# POEInjectorTop.net
KiCad netlist of a schematic drawn in Altium Designer
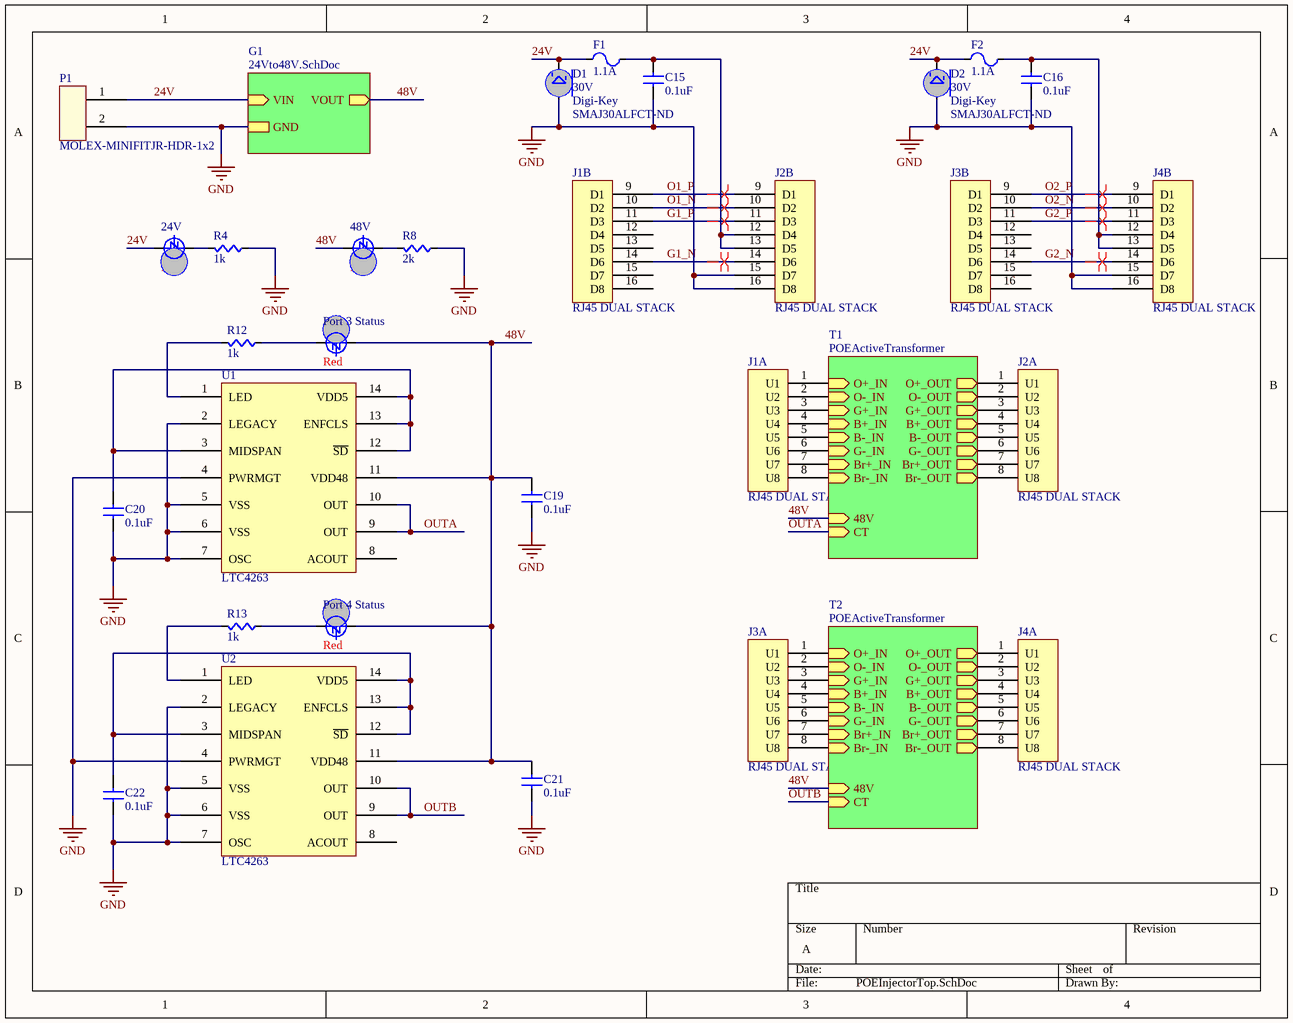
[diagram p0: POEInjectorTop.SchDoc]

(export (version "E")
  (design (tool "Eeschema 10.0.6"))
  (components
    (comp (ref "24V")
      (value "LED")
      (footprint "LED0603")
      (fields (field (name "COLOR") "Red"))
      (libsource (lib "") (part "LED_1"))
    )
    (comp (ref "48V")
      (value "LED")
      (footprint "LED0603")
      (fields (field (name "COLOR") "Red"))
      (libsource (lib "") (part "LED_1"))
    )
    (comp (ref "C15")
      (value "0.1uF")
      (footprint "CAPC0603")
      (fields (field (name "Comment") "Cap"))
      (libsource (lib "Passives") (part "Cap"))
    )
    (comp (ref "C16")
      (value "0.1uF")
      (footprint "CAPC0603")
      (fields (field (name "Comment") "Cap"))
      (libsource (lib "Passives") (part "Cap"))
    )
    (comp (ref "C19")
      (value "0.1uF")
      (footprint "CAPC0603")
      (fields (field (name "Comment") "Cap"))
      (libsource (lib "Passives") (part "Cap"))
    )
    (comp (ref "C20")
      (value "0.1uF")
      (footprint "CAPC0603")
      (fields (field (name "Comment") "Cap"))
      (libsource (lib "Passives") (part "Cap"))
    )
    (comp (ref "C21")
      (value "0.1uF")
      (footprint "CAPC0603")
      (fields (field (name "Comment") "Cap"))
      (libsource (lib "Passives") (part "Cap"))
    )
    (comp (ref "C22")
      (value "0.1uF")
      (footprint "CAPC0603")
      (fields (field (name "Comment") "Cap"))
      (libsource (lib "Passives") (part "Cap"))
    )
    (comp (ref "D1")
      (value "30V")
      (footprint "SMASeries")
      (description "Zener Diode")
      (fields
        (field (name "SUPPLIER 1") "Digi-Key")
        (field (name "SUPPLIER PART NUMBER 1") "SMAJ30ALFCT-ND")
        (field (name "Comment") "Zener")
      )
      (libsource (lib "Semiconductors") (part "Zener"))
    )
    (comp (ref "D2")
      (value "30V")
      (footprint "SMASeries")
      (description "Zener Diode")
      (fields
        (field (name "SUPPLIER 1") "Digi-Key")
        (field (name "SUPPLIER PART NUMBER 1") "SMAJ30ALFCT-ND")
        (field (name "Comment") "Zener")
      )
      (libsource (lib "Semiconductors") (part "Zener"))
    )
    (comp (ref "F1")
      (value "1.1A")
      (footprint "PTC7451X11N")
      (fields (field (name "Comment") "PTC Fuse"))
      (libsource (lib "Passives") (part "PTC_Fuse"))
    )
    (comp (ref "F2")
      (value "1.1A")
      (footprint "PTC7451X11N")
      (fields (field (name "Comment") "PTC Fuse"))
      (libsource (lib "Passives") (part "PTC_Fuse"))
    )
    (comp (ref "J1")
      (value "RJ45 DUAL STACK")
      (footprint "RJ45 DUAL STACK")
      (description "CONN MOD JACK 8P8C R/A SHIELDED")
      (libsource (lib "") (part "RJ45 DUAL STACK_1"))
    )
    (comp (ref "J2")
      (value "RJ45 DUAL STACK")
      (footprint "RJ45 DUAL STACK")
      (description "CONN MOD JACK 8P8C R/A SHIELDED")
      (libsource (lib "Connectors") (part "RJ45 DUAL STACK"))
    )
    (comp (ref "J3")
      (value "RJ45 DUAL STACK")
      (footprint "RJ45 DUAL STACK")
      (description "CONN MOD JACK 8P8C R/A SHIELDED")
      (libsource (lib "") (part "RJ45 DUAL STACK_1"))
    )
    (comp (ref "J4")
      (value "RJ45 DUAL STACK")
      (footprint "RJ45 DUAL STACK")
      (description "CONN MOD JACK 8P8C R/A SHIELDED")
      (libsource (lib "Connectors") (part "RJ45 DUAL STACK"))
    )
    (comp (ref "P1")
      (value "MOLEX-MINIFITJR-HDR-1x2")
      (footprint "MOLEX-MINIFITJR-HDR-1x2")
      (description "MINIFITJRHDR VT DR O/PGS 2POS")
      (libsource (lib "Connectors") (part "MOLEX-MINIFITJR-HDR-1x2"))
    )
    (comp (ref "Port 3 Status")
      (value "LED")
      (footprint "LED0603")
      (fields (field (name "COLOR") "Red"))
      (libsource (lib "Semiconductors") (part "LED"))
    )
    (comp (ref "Port 4 Status")
      (value "LED")
      (footprint "LED0603")
      (fields (field (name "COLOR") "Red"))
      (libsource (lib "Semiconductors") (part "LED"))
    )
    (comp (ref "R4")
      (value "1k")
      (footprint "RES0603")
      (fields (field (name "Comment") "Res"))
      (libsource (lib "Passives") (part "Res"))
    )
    (comp (ref "R8")
      (value "2k")
      (footprint "RES0603")
      (fields (field (name "Comment") "Res"))
      (libsource (lib "Passives") (part "Res"))
    )
    (comp (ref "R12")
      (value "1k")
      (footprint "RES0603")
      (fields (field (name "Comment") "Res"))
      (libsource (lib "Passives") (part "Res"))
    )
    (comp (ref "R13")
      (value "1k")
      (footprint "RES0603")
      (fields (field (name "Comment") "Res"))
      (libsource (lib "Passives") (part "Res"))
    )
    (comp (ref "U1")
      (value "LTC4263")
      (footprint "LTC4263")
      (description "IC POE 803.2AF SINGL PSE 14-SOIC")
      (libsource (lib "ICs") (part "LTC4263"))
    )
    (comp (ref "U2")
      (value "LTC4263")
      (footprint "LTC4263")
      (description "IC POE 803.2AF SINGL PSE 14-SOIC")
      (libsource (lib "ICs") (part "LTC4263"))
    )
  )
  (nets
    (net (code "1") (name "/24V") (class "Default")
      (node (ref "24V") (pin "A") (pinfunction "A_A") (pintype "passive"))
      (node (ref "D1") (pin "C") (pinfunction "C_C") (pintype "passive"))
      (node (ref "D2") (pin "C") (pinfunction "C_C") (pintype "passive"))
      (node (ref "F1") (pin "1") (pinfunction "A_1") (pintype "passive"))
      (node (ref "F2") (pin "1") (pinfunction "A_1") (pintype "passive"))
      (node (ref "P1") (pin "1") (pinfunction "1_1") (pintype "passive"))
    )
    (net (code "2") (name "/48V") (class "Default")
      (node (ref "48V") (pin "A") (pinfunction "A_A") (pintype "passive"))
      (node (ref "C19") (pin "1") (pinfunction "A_1") (pintype "passive"))
      (node (ref "C21") (pin "1") (pinfunction "A_1") (pintype "passive"))
      (node (ref "Port 3 Status") (pin "A") (pinfunction "A_A") (pintype "passive"))
      (node (ref "Port 4 Status") (pin "A") (pinfunction "A_A") (pintype "passive"))
      (node (ref "U1") (pin "11") (pinfunction "VDD48_11") (pintype "passive"))
      (node (ref "U2") (pin "11") (pinfunction "VDD48_11") (pintype "passive"))
    )
    (net (code "3") (name "/B+_IN") (class "Default")
      (node (ref "J3") (pin "4") (pinfunction "U4_4") (pintype "passive"))
    )
    (net (code "4") (name "/B+_IN_1") (class "Default")
      (node (ref "J1") (pin "4") (pinfunction "U4_4") (pintype "passive"))
    )
    (net (code "5") (name "/B+_OUT") (class "Default")
      (node (ref "J4") (pin "4") (pinfunction "U4_4") (pintype "passive"))
    )
    (net (code "6") (name "/B+_OUT_1") (class "Default")
      (node (ref "J2") (pin "4") (pinfunction "U4_4") (pintype "passive"))
    )
    (net (code "7") (name "/B-_IN") (class "Default")
      (node (ref "J3") (pin "5") (pinfunction "U5_5") (pintype "passive"))
    )
    (net (code "8") (name "/B-_IN_1") (class "Default")
      (node (ref "J1") (pin "5") (pinfunction "U5_5") (pintype "passive"))
    )
    (net (code "9") (name "/B-_OUT") (class "Default")
      (node (ref "J4") (pin "5") (pinfunction "U5_5") (pintype "passive"))
    )
    (net (code "10") (name "/B-_OUT_1") (class "Default")
      (node (ref "J2") (pin "5") (pinfunction "U5_5") (pintype "passive"))
    )
    (net (code "11") (name "/Br+_IN") (class "Default")
      (node (ref "J3") (pin "7") (pinfunction "U7_7") (pintype "passive"))
    )
    (net (code "12") (name "/Br+_IN_1") (class "Default")
      (node (ref "J1") (pin "7") (pinfunction "U7_7") (pintype "passive"))
    )
    (net (code "13") (name "/Br+_OUT") (class "Default")
      (node (ref "J4") (pin "7") (pinfunction "U7_7") (pintype "passive"))
    )
    (net (code "14") (name "/Br+_OUT_1") (class "Default")
      (node (ref "J2") (pin "7") (pinfunction "U7_7") (pintype "passive"))
    )
    (net (code "15") (name "/Br-_IN") (class "Default")
      (node (ref "J3") (pin "8") (pinfunction "U8_8") (pintype "passive"))
    )
    (net (code "16") (name "/Br-_IN_1") (class "Default")
      (node (ref "J1") (pin "8") (pinfunction "U8_8") (pintype "passive"))
    )
    (net (code "17") (name "/Br-_OUT") (class "Default")
      (node (ref "J4") (pin "8") (pinfunction "U8_8") (pintype "passive"))
    )
    (net (code "18") (name "/Br-_OUT_1") (class "Default")
      (node (ref "J2") (pin "8") (pinfunction "U8_8") (pintype "passive"))
    )
    (net (code "19") (name "/G+_IN") (class "Default")
      (node (ref "J3") (pin "3") (pinfunction "U3_3") (pintype "passive"))
    )
    (net (code "20") (name "/G+_IN_1") (class "Default")
      (node (ref "J1") (pin "3") (pinfunction "U3_3") (pintype "passive"))
    )
    (net (code "21") (name "/G+_OUT") (class "Default")
      (node (ref "J4") (pin "3") (pinfunction "U3_3") (pintype "passive"))
    )
    (net (code "22") (name "/G+_OUT_1") (class "Default")
      (node (ref "J2") (pin "3") (pinfunction "U3_3") (pintype "passive"))
    )
    (net (code "23") (name "/G-_IN") (class "Default")
      (node (ref "J3") (pin "6") (pinfunction "U6_6") (pintype "passive"))
    )
    (net (code "24") (name "/G-_IN_1") (class "Default")
      (node (ref "J1") (pin "6") (pinfunction "U6_6") (pintype "passive"))
    )
    (net (code "25") (name "/G-_OUT") (class "Default")
      (node (ref "J4") (pin "6") (pinfunction "U6_6") (pintype "passive"))
    )
    (net (code "26") (name "/G-_OUT_1") (class "Default")
      (node (ref "J2") (pin "6") (pinfunction "U6_6") (pintype "passive"))
    )
    (net (code "27") (name "/G1_N") (class "Default")
      (node (ref "J1") (pin "14") (pinfunction "D6_14") (pintype "passive"))
      (node (ref "J2") (pin "14") (pinfunction "D6_14") (pintype "passive"))
    )
    (net (code "28") (name "/G1_P") (class "Default")
      (node (ref "J1") (pin "11") (pinfunction "D3_11") (pintype "passive"))
      (node (ref "J2") (pin "11") (pinfunction "D3_11") (pintype "passive"))
    )
    (net (code "29") (name "/G2_N") (class "Default")
      (node (ref "J3") (pin "14") (pinfunction "D6_14") (pintype "passive"))
      (node (ref "J4") (pin "14") (pinfunction "D6_14") (pintype "passive"))
    )
    (net (code "30") (name "/G2_P") (class "Default")
      (node (ref "J3") (pin "11") (pinfunction "D3_11") (pintype "passive"))
      (node (ref "J4") (pin "11") (pinfunction "D3_11") (pintype "passive"))
    )
    (net (code "31") (name "/O+_IN") (class "Default")
      (node (ref "J3") (pin "1") (pinfunction "U1_1") (pintype "passive"))
    )
    (net (code "32") (name "/O+_IN_1") (class "Default")
      (node (ref "J1") (pin "1") (pinfunction "U1_1") (pintype "passive"))
    )
    (net (code "33") (name "/O+_OUT") (class "Default")
      (node (ref "J4") (pin "1") (pinfunction "U1_1") (pintype "passive"))
    )
    (net (code "34") (name "/O+_OUT_1") (class "Default")
      (node (ref "J2") (pin "1") (pinfunction "U1_1") (pintype "passive"))
    )
    (net (code "35") (name "/O-_IN") (class "Default")
      (node (ref "J3") (pin "2") (pinfunction "U2_2") (pintype "passive"))
    )
    (net (code "36") (name "/O-_IN_1") (class "Default")
      (node (ref "J1") (pin "2") (pinfunction "U2_2") (pintype "passive"))
    )
    (net (code "37") (name "/O-_OUT") (class "Default")
      (node (ref "J4") (pin "2") (pinfunction "U2_2") (pintype "passive"))
    )
    (net (code "38") (name "/O-_OUT_1") (class "Default")
      (node (ref "J2") (pin "2") (pinfunction "U2_2") (pintype "passive"))
    )
    (net (code "39") (name "/O1_N") (class "Default")
      (node (ref "J1") (pin "10") (pinfunction "D2_10") (pintype "passive"))
      (node (ref "J2") (pin "10") (pinfunction "D2_10") (pintype "passive"))
    )
    (net (code "40") (name "/O1_P") (class "Default")
      (node (ref "J1") (pin "9") (pinfunction "D1_9") (pintype "passive"))
      (node (ref "J2") (pin "9") (pinfunction "D1_9") (pintype "passive"))
    )
    (net (code "41") (name "/O2_N") (class "Default")
      (node (ref "J3") (pin "10") (pinfunction "D2_10") (pintype "passive"))
      (node (ref "J4") (pin "10") (pinfunction "D2_10") (pintype "passive"))
    )
    (net (code "42") (name "/O2_P") (class "Default")
      (node (ref "J3") (pin "9") (pinfunction "D1_9") (pintype "passive"))
      (node (ref "J4") (pin "9") (pinfunction "D1_9") (pintype "passive"))
    )
    (net (code "43") (name "/OUTA") (class "Default")
      (node (ref "U1") (pin "10") (pinfunction "OUT_10") (pintype "passive"))
      (node (ref "U1") (pin "9") (pinfunction "OUT_9") (pintype "passive"))
    )
    (net (code "44") (name "/OUTB") (class "Default")
      (node (ref "U2") (pin "10") (pinfunction "OUT_10") (pintype "passive"))
      (node (ref "U2") (pin "9") (pinfunction "OUT_9") (pintype "passive"))
    )
    (net (code "45") (name "GND") (class "Default")
      (node (ref "C15") (pin "2") (pinfunction "B_2") (pintype "passive"))
      (node (ref "C16") (pin "2") (pinfunction "B_2") (pintype "passive"))
      (node (ref "C19") (pin "2") (pinfunction "B_2") (pintype "passive"))
      (node (ref "C20") (pin "2") (pinfunction "B_2") (pintype "passive"))
      (node (ref "C21") (pin "2") (pinfunction "B_2") (pintype "passive"))
      (node (ref "C22") (pin "2") (pinfunction "B_2") (pintype "passive"))
      (node (ref "D1") (pin "A") (pinfunction "A_A") (pintype "passive"))
      (node (ref "D2") (pin "A") (pinfunction "A_A") (pintype "passive"))
      (node (ref "J2") (pin "15") (pinfunction "D7_15") (pintype "passive"))
      (node (ref "J2") (pin "16") (pinfunction "D8_16") (pintype "passive"))
      (node (ref "J4") (pin "15") (pinfunction "D7_15") (pintype "passive"))
      (node (ref "J4") (pin "16") (pinfunction "D8_16") (pintype "passive"))
      (node (ref "P1") (pin "2") (pinfunction "2_2") (pintype "passive"))
      (node (ref "R4") (pin "2") (pinfunction "B_2") (pintype "passive"))
      (node (ref "R8") (pin "2") (pinfunction "B_2") (pintype "passive"))
      (node (ref "U1") (pin "2") (pinfunction "LEGACY_2") (pintype "passive"))
      (node (ref "U1") (pin "4") (pinfunction "PWRMGT_4") (pintype "passive"))
      (node (ref "U1") (pin "5") (pinfunction "VSS_5") (pintype "passive"))
      (node (ref "U1") (pin "6") (pinfunction "VSS_6") (pintype "passive"))
      (node (ref "U1") (pin "7") (pinfunction "OSC_7") (pintype "passive"))
      (node (ref "U2") (pin "2") (pinfunction "LEGACY_2") (pintype "passive"))
      (node (ref "U2") (pin "4") (pinfunction "PWRMGT_4") (pintype "passive"))
      (node (ref "U2") (pin "5") (pinfunction "VSS_5") (pintype "passive"))
      (node (ref "U2") (pin "6") (pinfunction "VSS_6") (pintype "passive"))
      (node (ref "U2") (pin "7") (pinfunction "OSC_7") (pintype "passive"))
    )
    (net (code "46") (name "Net-(C15-A)") (class "Default")
      (node (ref "C15") (pin "1") (pinfunction "A_1") (pintype "passive"))
      (node (ref "F1") (pin "2") (pinfunction "B_2") (pintype "passive"))
      (node (ref "J2") (pin "12") (pinfunction "D4_12") (pintype "passive"))
      (node (ref "J2") (pin "13") (pinfunction "D5_13") (pintype "passive"))
    )
    (net (code "47") (name "Net-(C16-A)") (class "Default")
      (node (ref "C16") (pin "1") (pinfunction "A_1") (pintype "passive"))
      (node (ref "F2") (pin "2") (pinfunction "B_2") (pintype "passive"))
      (node (ref "J4") (pin "12") (pinfunction "D4_12") (pintype "passive"))
      (node (ref "J4") (pin "13") (pinfunction "D5_13") (pintype "passive"))
    )
    (net (code "48") (name "Net-(C20-A)") (class "Default")
      (node (ref "C20") (pin "1") (pinfunction "A_1") (pintype "passive"))
      (node (ref "U1") (pin "12") (pinfunction "~{SD}_12") (pintype "passive"))
      (node (ref "U1") (pin "13") (pinfunction "ENFCLS_13") (pintype "passive"))
      (node (ref "U1") (pin "14") (pinfunction "VDD5_14") (pintype "passive"))
      (node (ref "U1") (pin "3") (pinfunction "MIDSPAN_3") (pintype "passive"))
    )
    (net (code "49") (name "Net-(C22-A)") (class "Default")
      (node (ref "C22") (pin "1") (pinfunction "A_1") (pintype "passive"))
      (node (ref "U2") (pin "12") (pinfunction "~{SD}_12") (pintype "passive"))
      (node (ref "U2") (pin "13") (pinfunction "ENFCLS_13") (pintype "passive"))
      (node (ref "U2") (pin "14") (pinfunction "VDD5_14") (pintype "passive"))
      (node (ref "U2") (pin "3") (pinfunction "MIDSPAN_3") (pintype "passive"))
    )
    (net (code "50") (name "Net-(R4-A)") (class "Default")
      (node (ref "24V") (pin "C") (pinfunction "C_C") (pintype "passive"))
      (node (ref "R4") (pin "1") (pinfunction "A_1") (pintype "passive"))
    )
    (net (code "51") (name "Net-(R8-A)") (class "Default")
      (node (ref "48V") (pin "C") (pinfunction "C_C") (pintype "passive"))
      (node (ref "R8") (pin "1") (pinfunction "A_1") (pintype "passive"))
    )
    (net (code "52") (name "Net-(R12-A)") (class "Default")
      (node (ref "R12") (pin "1") (pinfunction "A_1") (pintype "passive"))
      (node (ref "U1") (pin "1") (pinfunction "LED_1") (pintype "passive"))
    )
    (net (code "53") (name "Net-(R12-B)") (class "Default")
      (node (ref "Port 3 Status") (pin "C") (pinfunction "C_C") (pintype "passive"))
      (node (ref "R12") (pin "2") (pinfunction "B_2") (pintype "passive"))
    )
    (net (code "54") (name "Net-(R13-A)") (class "Default")
      (node (ref "R13") (pin "1") (pinfunction "A_1") (pintype "passive"))
      (node (ref "U2") (pin "1") (pinfunction "LED_1") (pintype "passive"))
    )
    (net (code "55") (name "Net-(R13-B)") (class "Default")
      (node (ref "Port 4 Status") (pin "C") (pinfunction "C_C") (pintype "passive"))
      (node (ref "R13") (pin "2") (pinfunction "B_2") (pintype "passive"))
    )
    (net (code "56") (name "unconnected-(J1B-D4-Pad12)") (class "Default")
      (node (ref "J1") (pin "12") (pinfunction "D4_12") (pintype "passive"))
    )
    (net (code "57") (name "unconnected-(J1B-D5-Pad13)") (class "Default")
      (node (ref "J1") (pin "13") (pinfunction "D5_13") (pintype "passive"))
    )
    (net (code "58") (name "unconnected-(J1B-D7-Pad15)") (class "Default")
      (node (ref "J1") (pin "15") (pinfunction "D7_15") (pintype "passive"))
    )
    (net (code "59") (name "unconnected-(J1B-D8-Pad16)") (class "Default")
      (node (ref "J1") (pin "16") (pinfunction "D8_16") (pintype "passive"))
    )
    (net (code "60") (name "unconnected-(J3B-D4-Pad12)") (class "Default")
      (node (ref "J3") (pin "12") (pinfunction "D4_12") (pintype "passive"))
    )
    (net (code "61") (name "unconnected-(J3B-D5-Pad13)") (class "Default")
      (node (ref "J3") (pin "13") (pinfunction "D5_13") (pintype "passive"))
    )
    (net (code "62") (name "unconnected-(J3B-D7-Pad15)") (class "Default")
      (node (ref "J3") (pin "15") (pinfunction "D7_15") (pintype "passive"))
    )
    (net (code "63") (name "unconnected-(J3B-D8-Pad16)") (class "Default")
      (node (ref "J3") (pin "16") (pinfunction "D8_16") (pintype "passive"))
    )
    (net (code "64") (name "unconnected-(U1-ACOUT-Pad8)") (class "Default")
      (node (ref "U1") (pin "8") (pinfunction "ACOUT_8") (pintype "passive"))
    )
    (net (code "65") (name "unconnected-(U2-ACOUT-Pad8)") (class "Default")
      (node (ref "U2") (pin "8") (pinfunction "ACOUT_8") (pintype "passive"))
    )
  )
)
